# RCM-CommX1.net
KiCad netlist of a schematic drawn in EAGLE
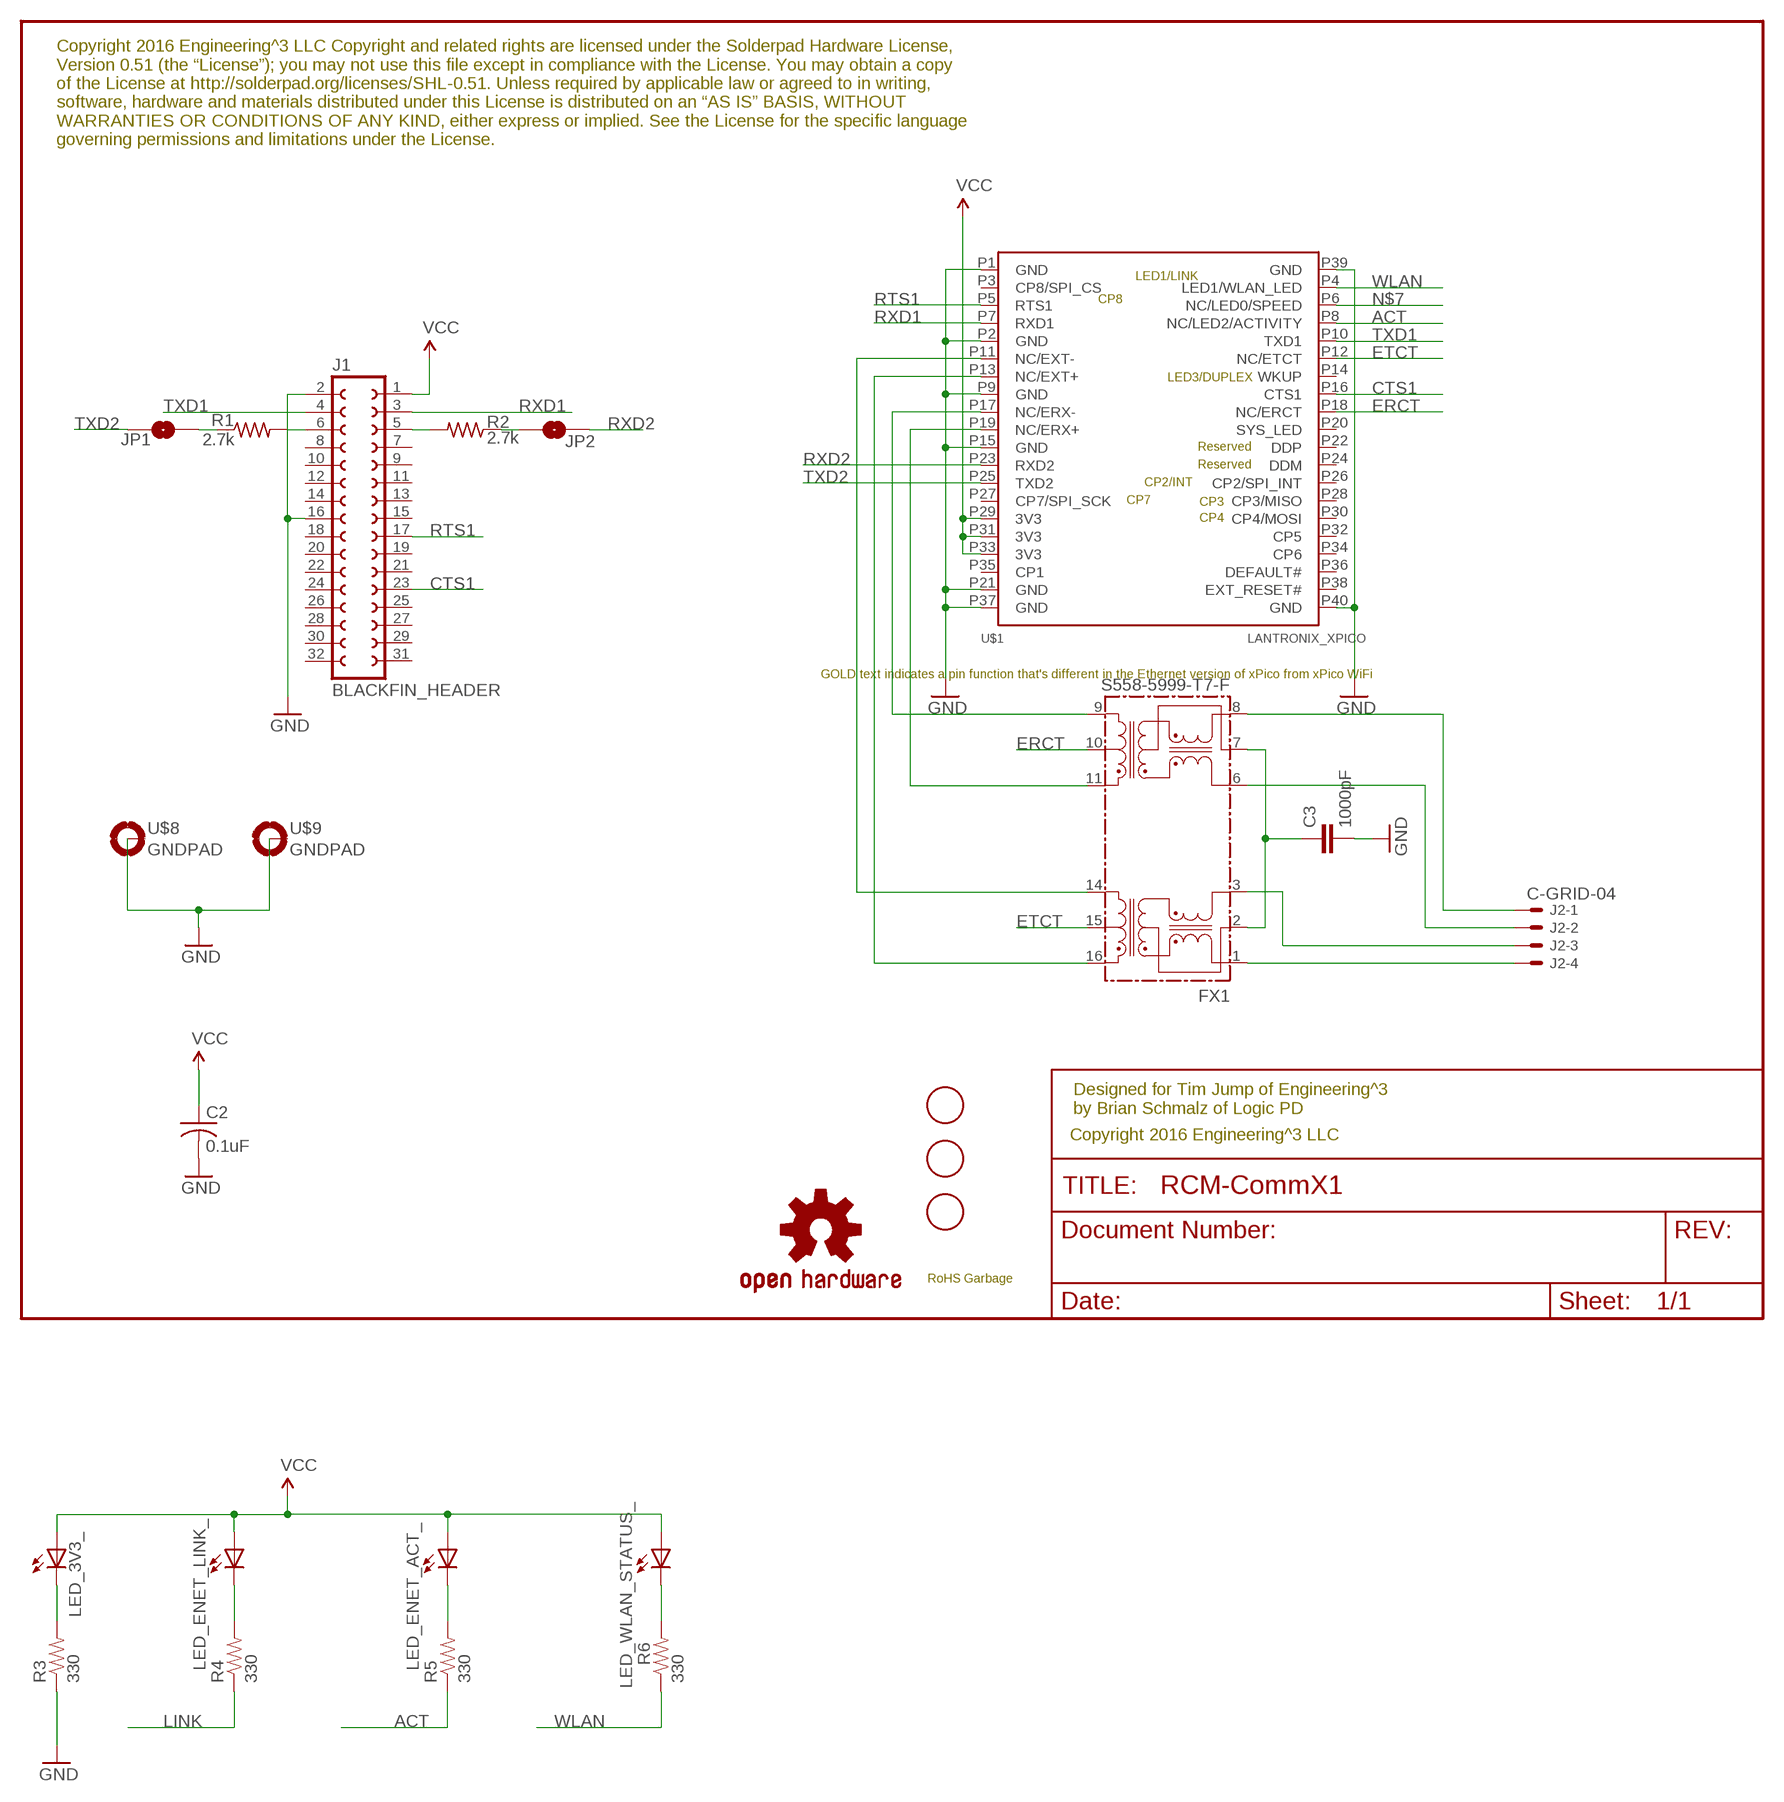
[diagram p0: schematic, sheet 1]

(export (version "E")
  (design (tool "Eeschema 10.0.6"))
  (components
    (comp (ref "C2")
      (value "0.1uF")
      (footprint "eagle-import:C0603")
      (libsource (lib "eagle-import") (part "C-USC0603"))
    )
    (comp (ref "C3")
      (value "1000pF")
      (footprint "eagle-import:0603-CAP")
      (libsource (lib "eagle-import") (part "CAP0603-CAP"))
    )
    (comp (ref "FID1")
      (value "FIDUCIAL")
      (footprint "eagle-import:FIDUCIAL_1MM")
      (libsource (lib "eagle-import") (part "FIDUCIAL"))
    )
    (comp (ref "FID2")
      (value "FIDUCIAL")
      (footprint "eagle-import:FIDUCIAL_1MM")
      (libsource (lib "eagle-import") (part "FIDUCIAL"))
    )
    (comp (ref "FID3")
      (value "FIDUCIAL")
      (footprint "eagle-import:FIDUCIAL_1MM")
      (libsource (lib "eagle-import") (part "FIDUCIAL"))
    )
    (comp (ref "FX1")
      (value "S558-5999-T7-F")
      (footprint "eagle-import:N5")
      (libsource (lib "eagle-import") (part "TG110-E050N5"))
    )
    (comp (ref "J1")
      (value "BLACKFIN_HEADER")
      (footprint "eagle-import:2X16")
      (libsource (lib "eagle-import") (part "BLACKFIN_HEADER"))
    )
    (comp (ref "J2-")
      (value "C-GRID-04")
      (footprint "eagle-import:70555-04")
      (libsource (lib "eagle-import") (part "C-GRID-04"))
    )
    (comp (ref "JP1")
      (value "JUMPER-PAD-2-NOROUND")
      (footprint "eagle-import:PAD-JUMPER-2-NO_YES_SILK_ROUND")
      (libsource (lib "eagle-import") (part "JUMPER-PAD-2-NOROUND"))
    )
    (comp (ref "JP2")
      (value "JUMPER-PAD-2-NOROUND")
      (footprint "eagle-import:PAD-JUMPER-2-NO_YES_SILK_ROUND")
      (libsource (lib "eagle-import") (part "JUMPER-PAD-2-NOROUND"))
    )
    (comp (ref "LED_3V3_")
      (value "LED0603")
      (footprint "eagle-import:LED-0603")
      (libsource (lib "eagle-import") (part "LED0603"))
    )
    (comp (ref "LED_ENET_ACT_")
      (value "LED0603")
      (footprint "eagle-import:LED-0603")
      (libsource (lib "eagle-import") (part "LED0603"))
    )
    (comp (ref "LED_ENET_LINK_")
      (value "LED0603")
      (footprint "eagle-import:LED-0603")
      (libsource (lib "eagle-import") (part "LED0603"))
    )
    (comp (ref "LED_WLAN_STATUS_")
      (value "LED0603")
      (footprint "eagle-import:LED-0603")
      (libsource (lib "eagle-import") (part "LED0603"))
    )
    (comp (ref "LOGO1")
      (value "OSHW-LOGOM")
      (footprint "eagle-import:OSHW-LOGO-M")
      (libsource (lib "eagle-import") (part "OSHW-LOGOM"))
    )
    (comp (ref "R1")
      (value "2.7k")
      (footprint "eagle-import:R0603")
      (libsource (lib "eagle-import") (part "R-US_R0603"))
    )
    (comp (ref "R2")
      (value "2.7k")
      (footprint "eagle-import:R0603")
      (libsource (lib "eagle-import") (part "R-US_R0603"))
    )
    (comp (ref "R3")
      (value "330")
      (footprint "eagle-import:0603-RES")
      (libsource (lib "eagle-import") (part "RESISTOR0603-RES"))
    )
    (comp (ref "R4")
      (value "330")
      (footprint "eagle-import:0603-RES")
      (libsource (lib "eagle-import") (part "RESISTOR0603-RES"))
    )
    (comp (ref "R5")
      (value "330")
      (footprint "eagle-import:0603-RES")
      (libsource (lib "eagle-import") (part "RESISTOR0603-RES"))
    )
    (comp (ref "R6")
      (value "330")
      (footprint "eagle-import:0603-RES")
      (libsource (lib "eagle-import") (part "RESISTOR0603-RES"))
    )
    (comp (ref "U$1")
      (value "LANTRONIX_XPICO")
      (footprint "eagle-import:LANTRONIX_XPICO")
      (libsource (lib "eagle-import") (part "LANTRONIX_XPICO"))
    )
    (comp (ref "U$3")
      (value "ROHS_GARBAGE")
      (footprint "eagle-import:ROHS_GARBAGE_5MM")
      (libsource (lib "eagle-import") (part "ROHS_GARBAGE"))
    )
    (comp (ref "U$8")
      (value "GNDPAD")
      (footprint "eagle-import:GNDPAD")
      (libsource (lib "eagle-import") (part "GNDPAD"))
    )
    (comp (ref "U$9")
      (value "GNDPAD")
      (footprint "eagle-import:GNDPAD")
      (libsource (lib "eagle-import") (part "GNDPAD"))
    )
  )
  (nets
    (net (code "1") (name "/ACT") (class "Default")
      (node (ref "R5") (pin "1") (pinfunction "1_1") (pintype "passive"))
      (node (ref "U$1") (pin "P8") (pinfunction "NC/LED2/ACTIVITY_P8") (pintype "bidirectional"))
    )
    (net (code "2") (name "/CTS1") (class "Default")
      (node (ref "J1") (pin "23") (pinfunction "GP6_23") (pintype "passive"))
      (node (ref "U$1") (pin "P16") (pinfunction "CTS1_P16") (pintype "bidirectional"))
    )
    (net (code "3") (name "/ERCT") (class "Default")
      (node (ref "FX1") (pin "10") (pinfunction "10_10") (pintype "passive"))
      (node (ref "U$1") (pin "P18") (pinfunction "NC/ERCT_P18") (pintype "bidirectional"))
    )
    (net (code "4") (name "/ETCT") (class "Default")
      (node (ref "FX1") (pin "15") (pinfunction "15_15") (pintype "passive"))
      (node (ref "U$1") (pin "P12") (pinfunction "NC/ETCT_P12") (pintype "bidirectional"))
    )
    (net (code "5") (name "/LINK") (class "Default")
      (node (ref "R4") (pin "1") (pinfunction "1_1") (pintype "passive"))
    )
    (net (code "6") (name "/N$7") (class "Default")
      (node (ref "U$1") (pin "P6") (pinfunction "NC/LED0/SPEED_P6") (pintype "bidirectional"))
    )
    (net (code "7") (name "/RTS1") (class "Default")
      (node (ref "J1") (pin "17") (pinfunction "GP0_17") (pintype "passive"))
      (node (ref "U$1") (pin "P5") (pinfunction "RTS1_P5") (pintype "bidirectional"))
    )
    (net (code "8") (name "/RXD1") (class "Default")
      (node (ref "J1") (pin "3") (pinfunction "TX0_3") (pintype "passive"))
      (node (ref "U$1") (pin "P7") (pinfunction "RXD1_P7") (pintype "bidirectional"))
    )
    (net (code "9") (name "/RXD2") (class "Default")
      (node (ref "JP2") (pin "2") (pinfunction "2_2") (pintype "passive"))
      (node (ref "U$1") (pin "P23") (pinfunction "RXD2_P23") (pintype "bidirectional"))
    )
    (net (code "10") (name "/TXD1") (class "Default")
      (node (ref "J1") (pin "4") (pinfunction "RX0_4") (pintype "passive"))
      (node (ref "U$1") (pin "P10") (pinfunction "TXD1_P10") (pintype "bidirectional"))
    )
    (net (code "11") (name "/TXD2") (class "Default")
      (node (ref "JP1") (pin "1") (pinfunction "1_1") (pintype "passive"))
      (node (ref "U$1") (pin "P25") (pinfunction "TXD2_P25") (pintype "bidirectional"))
    )
    (net (code "12") (name "/WLAN") (class "Default")
      (node (ref "R6") (pin "1") (pinfunction "1_1") (pintype "passive"))
      (node (ref "U$1") (pin "P4") (pinfunction "LED1/WLAN_LED_P4") (pintype "bidirectional"))
    )
    (net (code "13") (name "GND") (class "Default")
      (node (ref "C2") (pin "2") (pinfunction "2_2") (pintype "passive"))
      (node (ref "C3") (pin "2") (pinfunction "2_2") (pintype "passive"))
      (node (ref "J1") (pin "16") (pinfunction "GND16_16") (pintype "passive"))
      (node (ref "J1") (pin "2") (pinfunction "GND_2") (pintype "passive"))
      (node (ref "R3") (pin "1") (pinfunction "1_1") (pintype "passive"))
      (node (ref "U$1") (pin "P1") (pinfunction "GND_P1") (pintype "bidirectional"))
      (node (ref "U$1") (pin "P15") (pinfunction "GND_P15") (pintype "bidirectional"))
      (node (ref "U$1") (pin "P2") (pinfunction "GND_P2") (pintype "bidirectional"))
      (node (ref "U$1") (pin "P21") (pinfunction "GND_P21") (pintype "bidirectional"))
      (node (ref "U$1") (pin "P37") (pinfunction "GND_P37") (pintype "bidirectional"))
      (node (ref "U$1") (pin "P39") (pinfunction "GND_P39") (pintype "bidirectional"))
      (node (ref "U$1") (pin "P40") (pinfunction "GND_P40") (pintype "bidirectional"))
      (node (ref "U$1") (pin "P9") (pinfunction "GND_P9") (pintype "bidirectional"))
      (node (ref "U$8") (pin "P$1") (pinfunction "MOUNT_P$1") (pintype "passive"))
      (node (ref "U$9") (pin "P$1") (pinfunction "MOUNT_P$1") (pintype "passive"))
    )
    (net (code "14") (name "Net-(C3-Pad1)") (class "Default")
      (node (ref "C3") (pin "1") (pinfunction "1_1") (pintype "passive"))
      (node (ref "FX1") (pin "2") (pinfunction "2_2") (pintype "passive"))
      (node (ref "FX1") (pin "7") (pinfunction "7_7") (pintype "passive"))
    )
    (net (code "15") (name "Net-(J1-RX1)") (class "Default")
      (node (ref "J1") (pin "6") (pinfunction "RX1_6") (pintype "passive"))
      (node (ref "R1") (pin "2") (pinfunction "2_2") (pintype "passive"))
    )
    (net (code "16") (name "Net-(J1-TX1)") (class "Default")
      (node (ref "J1") (pin "5") (pinfunction "TX1_5") (pintype "passive"))
      (node (ref "R2") (pin "2") (pinfunction "2_2") (pintype "passive"))
    )
    (net (code "17") (name "Net-(J2-A-S)") (class "Default")
      (node (ref "FX1") (pin "8") (pinfunction "8_8") (pintype "passive"))
      (node (ref "J2-") (pin "1") (pinfunction "S_1") (pintype "passive"))
    )
    (net (code "18") (name "Net-(J2-B-S)") (class "Default")
      (node (ref "FX1") (pin "6") (pinfunction "6_6") (pintype "passive"))
      (node (ref "J2-") (pin "2") (pinfunction "S_2") (pintype "passive"))
    )
    (net (code "19") (name "Net-(J2-C-S)") (class "Default")
      (node (ref "FX1") (pin "3") (pinfunction "3_3") (pintype "passive"))
      (node (ref "J2-") (pin "3") (pinfunction "S_3") (pintype "passive"))
    )
    (net (code "20") (name "Net-(J2-D-S)") (class "Default")
      (node (ref "FX1") (pin "1") (pinfunction "1_1") (pintype "passive"))
      (node (ref "J2-") (pin "4") (pinfunction "S_4") (pintype "passive"))
    )
    (net (code "21") (name "Net-(JP1-Pad2)") (class "Default")
      (node (ref "JP1") (pin "2") (pinfunction "2_2") (pintype "passive"))
      (node (ref "R1") (pin "1") (pinfunction "1_1") (pintype "passive"))
    )
    (net (code "22") (name "Net-(JP2-Pad1)") (class "Default")
      (node (ref "JP2") (pin "1") (pinfunction "1_1") (pintype "passive"))
      (node (ref "R2") (pin "1") (pinfunction "1_1") (pintype "passive"))
    )
    (net (code "23") (name "Net-(LED_3V3_-PadC)") (class "Default")
      (node (ref "LED_3V3_") (pin "C") (pinfunction "C_C") (pintype "passive"))
      (node (ref "R3") (pin "2") (pinfunction "2_2") (pintype "passive"))
    )
    (net (code "24") (name "Net-(LED_ENET_ACT_-PadC)") (class "Default")
      (node (ref "LED_ENET_ACT_") (pin "C") (pinfunction "C_C") (pintype "passive"))
      (node (ref "R5") (pin "2") (pinfunction "2_2") (pintype "passive"))
    )
    (net (code "25") (name "Net-(LED_ENET_LINK_-PadC)") (class "Default")
      (node (ref "LED_ENET_LINK_") (pin "C") (pinfunction "C_C") (pintype "passive"))
      (node (ref "R4") (pin "2") (pinfunction "2_2") (pintype "passive"))
    )
    (net (code "26") (name "Net-(LED_WLAN_STATUS_-PadC)") (class "Default")
      (node (ref "LED_WLAN_STATUS_") (pin "C") (pinfunction "C_C") (pintype "passive"))
      (node (ref "R6") (pin "2") (pinfunction "2_2") (pintype "passive"))
    )
    (net (code "27") (name "Net-(U$1-NC{slash}ERX+)") (class "Default")
      (node (ref "FX1") (pin "11") (pinfunction "11_11") (pintype "passive"))
      (node (ref "U$1") (pin "P19") (pinfunction "NC/ERX+_P19") (pintype "bidirectional"))
    )
    (net (code "28") (name "Net-(U$1-NC{slash}ERX-)") (class "Default")
      (node (ref "FX1") (pin "9") (pinfunction "9_9") (pintype "passive"))
      (node (ref "U$1") (pin "P17") (pinfunction "NC/ERX-_P17") (pintype "bidirectional"))
    )
    (net (code "29") (name "Net-(U$1-NC{slash}EXT+)") (class "Default")
      (node (ref "FX1") (pin "16") (pinfunction "16_16") (pintype "passive"))
      (node (ref "U$1") (pin "P13") (pinfunction "NC/EXT+_P13") (pintype "bidirectional"))
    )
    (net (code "30") (name "Net-(U$1-NC{slash}EXT-)") (class "Default")
      (node (ref "FX1") (pin "14") (pinfunction "14_14") (pintype "passive"))
      (node (ref "U$1") (pin "P11") (pinfunction "NC/EXT-_P11") (pintype "bidirectional"))
    )
    (net (code "31") (name "VCC") (class "Default")
      (node (ref "C2") (pin "1") (pinfunction "1_1") (pintype "passive"))
      (node (ref "J1") (pin "1") (pinfunction "3.3V_1") (pintype "passive"))
      (node (ref "LED_3V3_") (pin "A") (pinfunction "A_A") (pintype "passive"))
      (node (ref "LED_ENET_ACT_") (pin "A") (pinfunction "A_A") (pintype "passive"))
      (node (ref "LED_ENET_LINK_") (pin "A") (pinfunction "A_A") (pintype "passive"))
      (node (ref "LED_WLAN_STATUS_") (pin "A") (pinfunction "A_A") (pintype "passive"))
      (node (ref "U$1") (pin "P29") (pinfunction "3V3_P29") (pintype "bidirectional"))
      (node (ref "U$1") (pin "P31") (pinfunction "3V3_P31") (pintype "bidirectional"))
      (node (ref "U$1") (pin "P33") (pinfunction "3V3_P33") (pintype "bidirectional"))
    )
    (net (code "32") (name "unconnected-(J1-GP1-Pad18)") (class "Default")
      (node (ref "J1") (pin "18") (pinfunction "GP1_18") (pintype "passive"))
    )
    (net (code "33") (name "unconnected-(J1-GP2-Pad19)") (class "Default")
      (node (ref "J1") (pin "19") (pinfunction "GP2_19") (pintype "passive"))
    )
    (net (code "34") (name "unconnected-(J1-GP3-Pad20)") (class "Default")
      (node (ref "J1") (pin "20") (pinfunction "GP3_20") (pintype "passive"))
    )
    (net (code "35") (name "unconnected-(J1-GP4-Pad21)") (class "Default")
      (node (ref "J1") (pin "21") (pinfunction "GP4_21") (pintype "passive"))
    )
    (net (code "36") (name "unconnected-(J1-GP5-Pad22)") (class "Default")
      (node (ref "J1") (pin "22") (pinfunction "GP5_22") (pintype "passive"))
    )
    (net (code "37") (name "unconnected-(J1-GP7-Pad24)") (class "Default")
      (node (ref "J1") (pin "24") (pinfunction "GP7_24") (pintype "passive"))
    )
    (net (code "38") (name "unconnected-(J1-GP8-Pad25)") (class "Default")
      (node (ref "J1") (pin "25") (pinfunction "GP8_25") (pintype "passive"))
    )
    (net (code "39") (name "unconnected-(J1-GP9-Pad26)") (class "Default")
      (node (ref "J1") (pin "26") (pinfunction "GP9_26") (pintype "passive"))
    )
    (net (code "40") (name "unconnected-(J1-GPA-Pad27)") (class "Default")
      (node (ref "J1") (pin "27") (pinfunction "GPA_27") (pintype "passive"))
    )
    (net (code "41") (name "unconnected-(J1-GPB-Pad28)") (class "Default")
      (node (ref "J1") (pin "28") (pinfunction "GPB_28") (pintype "passive"))
    )
    (net (code "42") (name "unconnected-(J1-GPC-Pad29)") (class "Default")
      (node (ref "J1") (pin "29") (pinfunction "GPC_29") (pintype "passive"))
    )
    (net (code "43") (name "unconnected-(J1-GPD-Pad30)") (class "Default")
      (node (ref "J1") (pin "30") (pinfunction "GPD_30") (pintype "passive"))
    )
    (net (code "44") (name "unconnected-(J1-GPE-Pad31)") (class "Default")
      (node (ref "J1") (pin "31") (pinfunction "GPE_31") (pintype "passive"))
    )
    (net (code "45") (name "unconnected-(J1-GPF-Pad32)") (class "Default")
      (node (ref "J1") (pin "32") (pinfunction "GPF_32") (pintype "passive"))
    )
    (net (code "46") (name "unconnected-(J1-I2C_SDA-Pad15)") (class "Default")
      (node (ref "J1") (pin "15") (pinfunction "I2C_SDA_15") (pintype "passive"))
    )
    (net (code "47") (name "unconnected-(J1-SPI_MISO-Pad10)") (class "Default")
      (node (ref "J1") (pin "10") (pinfunction "SPI_MISO_10") (pintype "passive"))
    )
    (net (code "48") (name "unconnected-(J1-SPI_MOSI-Pad9)") (class "Default")
      (node (ref "J1") (pin "9") (pinfunction "SPI_MOSI_9") (pintype "passive"))
    )
    (net (code "49") (name "unconnected-(J1-SPI_SCK-Pad11)") (class "Default")
      (node (ref "J1") (pin "11") (pinfunction "SPI_SCK_11") (pintype "passive"))
    )
    (net (code "50") (name "unconnected-(J1-SPI_SCL-Pad14)") (class "Default")
      (node (ref "J1") (pin "14") (pinfunction "SPI_SCL_14") (pintype "passive"))
    )
    (net (code "51") (name "unconnected-(J1-SPI_SEL-Pad12)") (class "Default")
      (node (ref "J1") (pin "12") (pinfunction "SPI_SEL_12") (pintype "passive"))
    )
    (net (code "52") (name "unconnected-(J1-SPI_SEL2-Pad13)") (class "Default")
      (node (ref "J1") (pin "13") (pinfunction "SPI_SEL2_13") (pintype "passive"))
    )
    (net (code "53") (name "unconnected-(J1-TMR2-Pad7)") (class "Default")
      (node (ref "J1") (pin "7") (pinfunction "TMR2_7") (pintype "passive"))
    )
    (net (code "54") (name "unconnected-(J1-TMR3-Pad8)") (class "Default")
      (node (ref "J1") (pin "8") (pinfunction "TMR3_8") (pintype "passive"))
    )
    (net (code "55") (name "unconnected-(U$1-CP1-PadP35)") (class "Default")
      (node (ref "U$1") (pin "P35") (pinfunction "CP1_P35") (pintype "bidirectional"))
    )
    (net (code "56") (name "unconnected-(U$1-CP2{slash}SPI_INT-PadP26)") (class "Default")
      (node (ref "U$1") (pin "P26") (pinfunction "CP2/SPI_INT_P26") (pintype "bidirectional"))
    )
    (net (code "57") (name "unconnected-(U$1-CP3{slash}MISO-PadP28)") (class "Default")
      (node (ref "U$1") (pin "P28") (pinfunction "CP3/MISO_P28") (pintype "bidirectional"))
    )
    (net (code "58") (name "unconnected-(U$1-CP4{slash}MOSI-PadP30)") (class "Default")
      (node (ref "U$1") (pin "P30") (pinfunction "CP4/MOSI_P30") (pintype "bidirectional"))
    )
    (net (code "59") (name "unconnected-(U$1-CP5-PadP32)") (class "Default")
      (node (ref "U$1") (pin "P32") (pinfunction "CP5_P32") (pintype "bidirectional"))
    )
    (net (code "60") (name "unconnected-(U$1-CP6-PadP34)") (class "Default")
      (node (ref "U$1") (pin "P34") (pinfunction "CP6_P34") (pintype "bidirectional"))
    )
    (net (code "61") (name "unconnected-(U$1-CP7{slash}SPI_SCK-PadP27)") (class "Default")
      (node (ref "U$1") (pin "P27") (pinfunction "CP7/SPI_SCK_P27") (pintype "bidirectional"))
    )
    (net (code "62") (name "unconnected-(U$1-CP8{slash}SPI_CS-PadP3)") (class "Default")
      (node (ref "U$1") (pin "P3") (pinfunction "CP8/SPI_CS_P3") (pintype "bidirectional"))
    )
    (net (code "63") (name "unconnected-(U$1-DDM-PadP24)") (class "Default")
      (node (ref "U$1") (pin "P24") (pinfunction "DDM_P24") (pintype "bidirectional"))
    )
    (net (code "64") (name "unconnected-(U$1-DDP-PadP22)") (class "Default")
      (node (ref "U$1") (pin "P22") (pinfunction "DDP_P22") (pintype "bidirectional"))
    )
    (net (code "65") (name "unconnected-(U$1-DEFAULT#-PadP36)") (class "Default")
      (node (ref "U$1") (pin "P36") (pinfunction "DEFAULT#_P36") (pintype "bidirectional"))
    )
    (net (code "66") (name "unconnected-(U$1-EXT_RESET#-PadP38)") (class "Default")
      (node (ref "U$1") (pin "P38") (pinfunction "EXT_RESET#_P38") (pintype "bidirectional"))
    )
    (net (code "67") (name "unconnected-(U$1-SYS_LED-PadP20)") (class "Default")
      (node (ref "U$1") (pin "P20") (pinfunction "SYS_LED_P20") (pintype "bidirectional"))
    )
    (net (code "68") (name "unconnected-(U$1-WKUP-PadP14)") (class "Default")
      (node (ref "U$1") (pin "P14") (pinfunction "WKUP_P14") (pintype "bidirectional"))
    )
  )
)
